# Node_ADE.net
KiCad netlist of a schematic drawn in Altium Designer
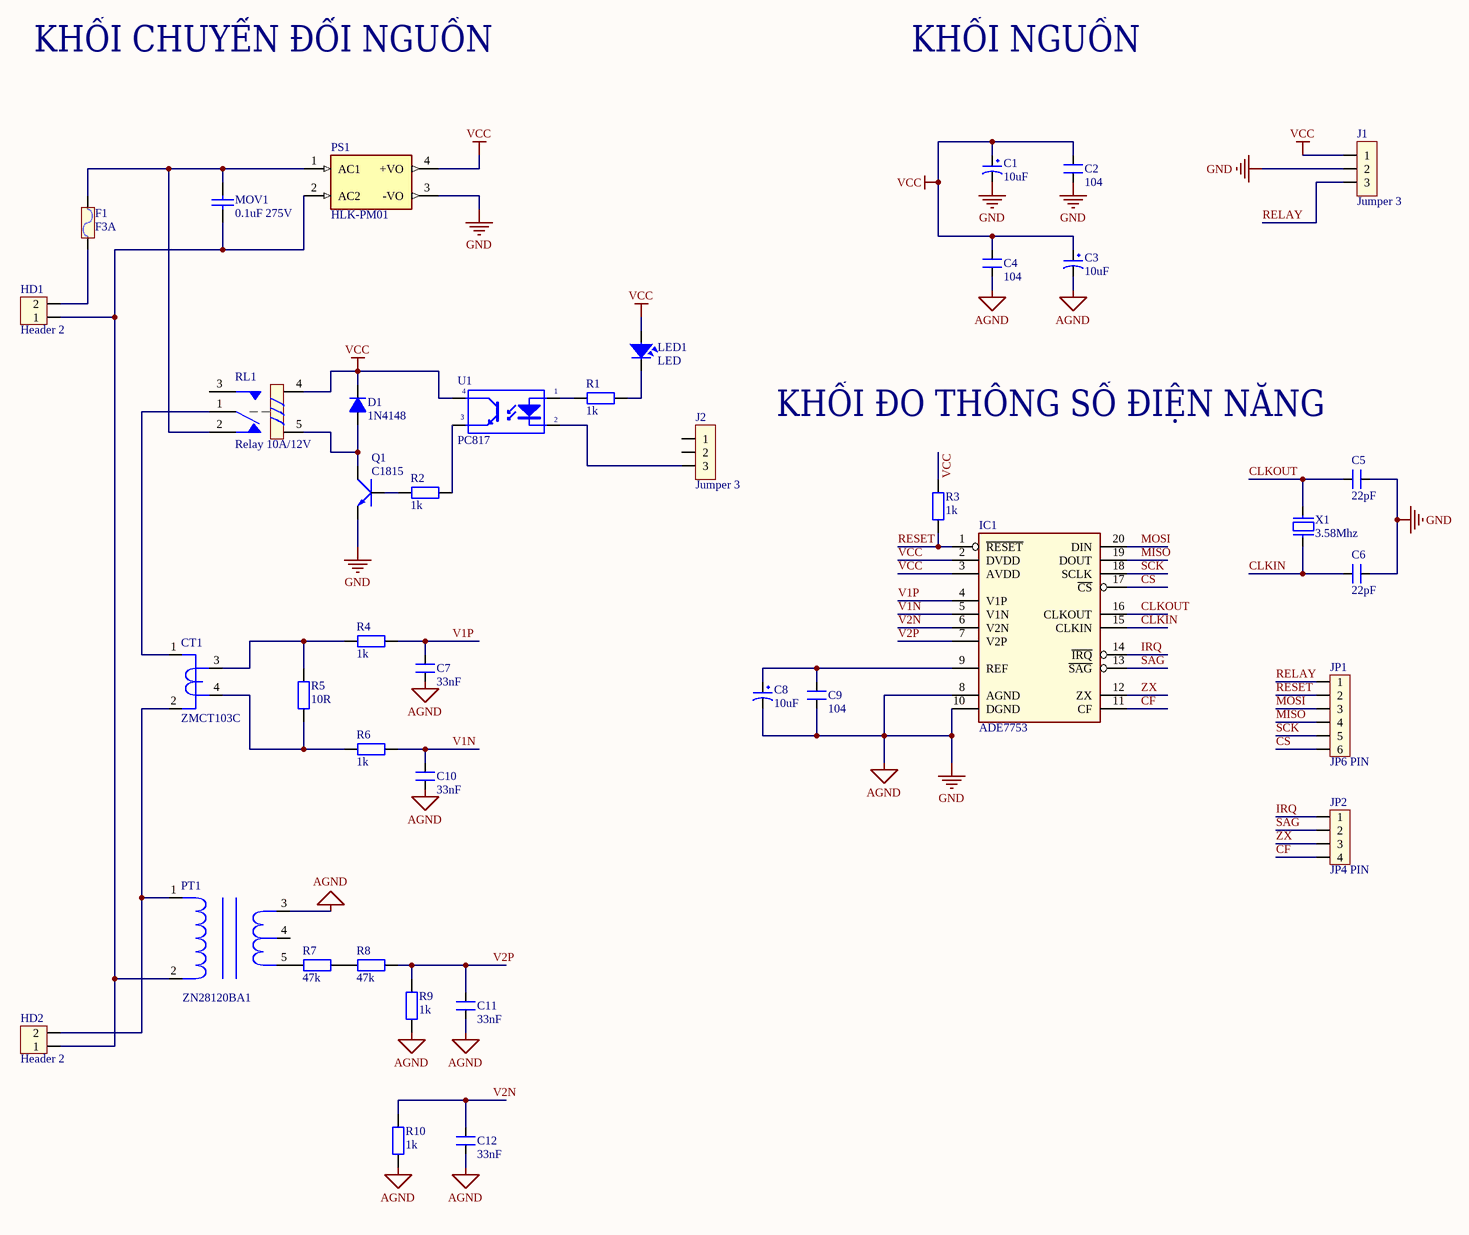
[diagram p0: Node_ADE.SchDoc]

(export (version "E")
  (design (tool "Eeschema 10.0.6"))
  (components
    (comp (ref "C1")
      (value "10uF")
      (footprint "CP1/2")
      (description "Cap P  0,1uF < 22uF , 16 - 50V")
      (libsource (lib "VioletofSun") (part "CP1"))
    )
    (comp (ref "C2")
      (value "104")
      (footprint "CN2")
      (description "Cap np 104 => 105pF")
      (libsource (lib "syhaunguyen") (part "CN2"))
    )
    (comp (ref "C3")
      (value "10uF")
      (footprint "CP1/2")
      (description "Cap P  0,1uF < 22uF , 16 - 50V")
      (libsource (lib "VioletofSun") (part "CP1"))
    )
    (comp (ref "C4")
      (value "104")
      (footprint "CN2")
      (description "Cap np 104 => 105pF")
      (libsource (lib "syhaunguyen") (part "CN2"))
    )
    (comp (ref "C5")
      (value "22pF")
      (footprint "CN1")
      (description "Cremic For Xtal 1pF => 100pF")
      (libsource (lib "syhaunguyen") (part "CN0"))
    )
    (comp (ref "C6")
      (value "22pF")
      (footprint "CN1")
      (description "Cremic For Xtal 1pF => 100pF")
      (libsource (lib "syhaunguyen") (part "CN0"))
    )
    (comp (ref "C7")
      (value "33nF")
      (footprint "CN1")
      (description "Cremic For Xtal 1pF => 100pF")
      (libsource (lib "VioletofSun") (part "CN0"))
    )
    (comp (ref "C8")
      (value "10uF")
      (footprint "CP1/2")
      (description "Cap P  0,1uF < 22uF , 16 - 50V")
      (libsource (lib "VioletofSun") (part "CP1"))
    )
    (comp (ref "C9")
      (value "104")
      (footprint "CN2")
      (description "Cap np 104 => 105pF")
      (libsource (lib "syhaunguyen") (part "CN2"))
    )
    (comp (ref "C10")
      (value "33nF")
      (footprint "CN1")
      (description "Cremic For Xtal 1pF => 100pF")
      (libsource (lib "VioletofSun") (part "CN0"))
    )
    (comp (ref "C11")
      (value "33nF")
      (footprint "CN1")
      (description "Cremic For Xtal 1pF => 100pF")
      (libsource (lib "VioletofSun") (part "CN0"))
    )
    (comp (ref "C12")
      (value "33nF")
      (footprint "CN1")
      (description "Cremic For Xtal 1pF => 100pF")
      (libsource (lib "VioletofSun") (part "CN0"))
    )
    (comp (ref "CT1")
      (value "ZMCT103C")
      (footprint "ZMCT103C:ZMCT103C")
      (description "ZMCT103C Current Transformer 1000:1 5A/5mA")
      (libsource (lib "ZMCT103C") (part "ZMCT103C"))
    )
    (comp (ref "D1")
      (value "1N4148")
      (footprint "D0.5A")
      (description "D0.5A")
      (libsource (lib "syhaunguyen") (part "D0.5A"))
    )
    (comp (ref "F1")
      (value "F3A")
      (footprint "FUSE2")
      (description "Fuse")
      (fields (field (name "DESIGNED BY") "VanDungEvn"))
      (libsource (lib "syhaunguyen") (part "Fuse"))
    )
    (comp (ref "HD1")
      (value "Header 2")
      (footprint "HED2")
      (description "Header 2 (Green)")
      (libsource (lib "syhaunguyen") (part "Hed2"))
    )
    (comp (ref "HD2")
      (value "Header 2")
      (footprint "HED2")
      (description "Header 2 (Green)")
      (libsource (lib "syhaunguyen") (part "Hed2"))
    )
    (comp (ref "IC1")
      (value "ADE7753")
      (footprint "TSOP65-20BN")
      (description "Single-Phase Multifunction Metering IC with di/dt Sensor Interface")
      (libsource (lib "syhaunguyen") (part "ADE7753"))
    )
    (comp (ref "J1") (value "Jumper 3") (footprint "JP3") (libsource (lib "syhaunguyen") (part "JP3")))
    (comp (ref "J2") (value "Jumper 3") (footprint "JP3") (libsource (lib "syhaunguyen") (part "JP3")))
    (comp (ref "JP1") (value "JP6 PIN") (footprint "JP6") (libsource (lib "syhaunguyen") (part "JP6")))
    (comp (ref "JP2") (value "JP4 PIN") (footprint "JP4") (libsource (lib "Cty1") (part "JP4")))
    (comp (ref "LED1")
      (value "LED")
      (footprint "LED-3")
      (description "LED Single colour Green and Red")
      (libsource (lib "syhaunguyen") (part "LED"))
    )
    (comp (ref "MOV1")
      (value "0.1uF 275V")
      (footprint "CAP_1uF")
      (description "Capacitor 0.1uF 275V")
      (libsource (lib "My IC") (part "Cap DIP"))
    )
    (comp (ref "PS1")
      (value "HLK-PM01")
      (footprint "CONV_HLK-PM01")
      (fields (field (name "MF") "Hi-link") (field (name "MP") "hlk-pm01"))
      (libsource (lib "HLK-PM01") (part "HLK-PM01"))
    )
    (comp (ref "PT1")
      (value "ZN28120BA1")
      (footprint "ZN28120BA1")
      (description "220VAC / 12VAC EI28 ZN28120BA1")
      (libsource (lib "ZN28120BA1") (part "EI28 ZN28120BA1"))
    )
    (comp (ref "Q1")
      (value "C1815")
      (footprint "QTO-92")
      (description "NPN 600mW, ECB")
      (libsource (lib "VioletofSun") (part "C1815"))
    )
    (comp (ref "R1")
      (value "1k")
      (footprint "R1/4W")
      (description "Resistor 1/4W")
      (libsource (lib "syhaunguyen") (part "R1/4W"))
    )
    (comp (ref "R2")
      (value "1k")
      (footprint "R1/4W")
      (description "Resistor 1/4W")
      (libsource (lib "syhaunguyen") (part "R1/4W"))
    )
    (comp (ref "R3")
      (value "1k")
      (footprint "R1/4W")
      (description "Resistor 1/4W")
      (libsource (lib "syhaunguyen") (part "R1/4W"))
    )
    (comp (ref "R4")
      (value "1k")
      (footprint "R1/4W")
      (description "Resistor 1/4W")
      (libsource (lib "syhaunguyen") (part "R1/4W"))
    )
    (comp (ref "R5")
      (value "10R")
      (footprint "R1/2W")
      (description "Resistor 1/4W")
      (libsource (lib "syhaunguyen") (part "R1/4W"))
    )
    (comp (ref "R6")
      (value "1k")
      (footprint "R1/4W")
      (description "Resistor 1/4W")
      (libsource (lib "syhaunguyen") (part "R1/4W"))
    )
    (comp (ref "R7")
      (value "47k")
      (footprint "R1/4W")
      (description "Resistor 1/4W")
      (libsource (lib "syhaunguyen") (part "R1/4W"))
    )
    (comp (ref "R8")
      (value "47k")
      (footprint "R1/4W")
      (description "Resistor 1/4W")
      (libsource (lib "syhaunguyen") (part "R1/4W"))
    )
    (comp (ref "R9")
      (value "1k")
      (footprint "R1/4W")
      (description "Resistor 1/4W")
      (libsource (lib "syhaunguyen") (part "R1/4W"))
    )
    (comp (ref "R10")
      (value "1k")
      (footprint "R1/4W")
      (description "Resistor 1/4W")
      (libsource (lib "syhaunguyen") (part "R1/4W"))
    )
    (comp (ref "RL1")
      (value "Relay 10A/12V")
      (footprint "RL_SPDT_10A")
      (description "Relay SPDT,10A - 12VDC 5 Pin")
      (libsource (lib "syhaunguyen") (part "Relay 1"))
    )
    (comp (ref "U1")
      (value "PC817")
      (footprint "DIP4/W0.3")
      (description "Single Opto")
      (libsource (lib "syhaunguyen") (part "PC817"))
    )
    (comp (ref "X1")
      (value "3.58Mhz")
      (footprint "XT2")
      (description "Crystal For all Crystal 2pin.")
      (libsource (lib "syhaunguyen") (part "XT2"))
    )
  )
  (nets
    (net (code "2") (name "/CF") (class "Default")
      (node (ref "IC1") (pin "11") (pinfunction "CF_11") (pintype "passive"))
      (node (ref "JP2") (pin "4") (pinfunction "4_4") (pintype "passive"))
    )
    (net (code "3") (name "/CLKIN") (class "Default")
      (node (ref "C6") (pin "1") (pinfunction "1_1") (pintype "passive"))
      (node (ref "IC1") (pin "15") (pinfunction "CLKIN_15") (pintype "passive"))
      (node (ref "X1") (pin "1") (pinfunction "1_1") (pintype "passive"))
    )
    (net (code "4") (name "/CLKOUT") (class "Default")
      (node (ref "C5") (pin "1") (pinfunction "1_1") (pintype "passive"))
      (node (ref "IC1") (pin "16") (pinfunction "CLKOUT_16") (pintype "passive"))
      (node (ref "X1") (pin "2") (pinfunction "2_2") (pintype "passive"))
    )
    (net (code "5") (name "/CS") (class "Default")
      (node (ref "IC1") (pin "17") (pinfunction "~{CS}_17") (pintype "passive"))
      (node (ref "JP1") (pin "6") (pinfunction "6_6") (pintype "passive"))
    )
    (net (code "6") (name "/IRQ") (class "Default")
      (node (ref "IC1") (pin "14") (pinfunction "~{IRQ}_14") (pintype "passive"))
      (node (ref "JP2") (pin "1") (pinfunction "1_1") (pintype "passive"))
    )
    (net (code "7") (name "/MISO") (class "Default")
      (node (ref "IC1") (pin "19") (pinfunction "DOUT_19") (pintype "passive"))
      (node (ref "JP1") (pin "4") (pinfunction "4_4") (pintype "passive"))
    )
    (net (code "8") (name "/MOSI") (class "Default")
      (node (ref "IC1") (pin "20") (pinfunction "DIN_20") (pintype "passive"))
      (node (ref "JP1") (pin "3") (pinfunction "3_3") (pintype "passive"))
    )
    (net (code "9") (name "/RELAY") (class "Default")
      (node (ref "J1") (pin "3") (pinfunction "3_3") (pintype "passive"))
      (node (ref "JP1") (pin "1") (pinfunction "1_1") (pintype "passive"))
    )
    (net (code "10") (name "/RESET") (class "Default")
      (node (ref "IC1") (pin "1") (pinfunction "~{RESET}_1") (pintype "passive"))
      (node (ref "JP1") (pin "2") (pinfunction "2_2") (pintype "passive"))
      (node (ref "R3") (pin "1") (pinfunction "1_1") (pintype "passive"))
    )
    (net (code "11") (name "/SAG") (class "Default")
      (node (ref "IC1") (pin "13") (pinfunction "~{SAG}_13") (pintype "passive"))
      (node (ref "JP2") (pin "2") (pinfunction "2_2") (pintype "passive"))
    )
    (net (code "12") (name "/SCK") (class "Default")
      (node (ref "IC1") (pin "18") (pinfunction "SCLK_18") (pintype "passive"))
      (node (ref "JP1") (pin "5") (pinfunction "5_5") (pintype "passive"))
    )
    (net (code "13") (name "/V1N") (class "Default")
      (node (ref "C10") (pin "2") (pinfunction "2_2") (pintype "passive"))
      (node (ref "IC1") (pin "5") (pinfunction "V1N_5") (pintype "passive"))
      (node (ref "R6") (pin "2") (pinfunction "2_2") (pintype "passive"))
    )
    (net (code "14") (name "/V1P") (class "Default")
      (node (ref "C7") (pin "2") (pinfunction "2_2") (pintype "passive"))
      (node (ref "IC1") (pin "4") (pinfunction "V1P_4") (pintype "passive"))
      (node (ref "R4") (pin "2") (pinfunction "2_2") (pintype "passive"))
    )
    (net (code "15") (name "/V2N") (class "Default")
      (node (ref "C12") (pin "2") (pinfunction "2_2") (pintype "passive"))
      (node (ref "IC1") (pin "6") (pinfunction "V2N_6") (pintype "passive"))
      (node (ref "R10") (pin "2") (pinfunction "2_2") (pintype "passive"))
    )
    (net (code "16") (name "/V2P") (class "Default")
      (node (ref "C11") (pin "2") (pinfunction "2_2") (pintype "passive"))
      (node (ref "IC1") (pin "7") (pinfunction "V2P_7") (pintype "passive"))
      (node (ref "R8") (pin "2") (pinfunction "2_2") (pintype "passive"))
      (node (ref "R9") (pin "2") (pinfunction "2_2") (pintype "passive"))
    )
    (net (code "17") (name "/ZX") (class "Default")
      (node (ref "IC1") (pin "12") (pinfunction "ZX_12") (pintype "passive"))
      (node (ref "JP2") (pin "3") (pinfunction "3_3") (pintype "passive"))
    )
    (net (code "18") (name "AGND") (class "Default")
      (node (ref "C1") (pin "2") (pinfunction "2_2") (pintype "passive"))
      (node (ref "C10") (pin "1") (pinfunction "1_1") (pintype "passive"))
      (node (ref "C11") (pin "1") (pinfunction "1_1") (pintype "passive"))
      (node (ref "C12") (pin "1") (pinfunction "1_1") (pintype "passive"))
      (node (ref "C2") (pin "1") (pinfunction "1_1") (pintype "passive"))
      (node (ref "C3") (pin "2") (pinfunction "2_2") (pintype "passive"))
      (node (ref "C4") (pin "1") (pinfunction "1_1") (pintype "passive"))
      (node (ref "C5") (pin "2") (pinfunction "2_2") (pintype "passive"))
      (node (ref "C6") (pin "2") (pinfunction "2_2") (pintype "passive"))
      (node (ref "C7") (pin "1") (pinfunction "1_1") (pintype "passive"))
      (node (ref "C8") (pin "2") (pinfunction "2_2") (pintype "passive"))
      (node (ref "C9") (pin "1") (pinfunction "1_1") (pintype "passive"))
      (node (ref "IC1") (pin "10") (pinfunction "DGND_10") (pintype "passive"))
      (node (ref "IC1") (pin "8") (pinfunction "AGND_8") (pintype "passive"))
      (node (ref "J1") (pin "2") (pinfunction "2_2") (pintype "passive"))
      (node (ref "PS1") (pin "3") (pinfunction "-VO_3") (pintype "output"))
      (node (ref "PT1") (pin "3") (pinfunction "3_3") (pintype "passive"))
      (node (ref "Q1") (pin "1") (pinfunction "E_1") (pintype "passive"))
      (node (ref "R10") (pin "1") (pinfunction "1_1") (pintype "passive"))
      (node (ref "R9") (pin "1") (pinfunction "1_1") (pintype "passive"))
    )
    (net (code "19") (name "Net-(CT1-Pad1)") (class "Default")
      (node (ref "CT1") (pin "1") (pinfunction "1_1") (pintype "passive"))
      (node (ref "RL1") (pin "1") (pinfunction "1_1") (pintype "passive"))
    )
    (net (code "20") (name "Net-(CT1-Pad2)") (class "Default")
      (node (ref "CT1") (pin "2") (pinfunction "2_2") (pintype "passive"))
      (node (ref "HD2") (pin "2") (pinfunction "2_2") (pintype "passive"))
      (node (ref "PT1") (pin "1") (pinfunction "1_1") (pintype "passive"))
    )
    (net (code "21") (name "Net-(CT1-Pad3)") (class "Default")
      (node (ref "CT1") (pin "3") (pinfunction "3_3") (pintype "passive"))
      (node (ref "R4") (pin "1") (pinfunction "1_1") (pintype "passive"))
      (node (ref "R5") (pin "2") (pinfunction "2_2") (pintype "passive"))
    )
    (net (code "22") (name "Net-(CT1-Pad4)") (class "Default")
      (node (ref "CT1") (pin "4") (pinfunction "4_4") (pintype "passive"))
      (node (ref "R5") (pin "1") (pinfunction "1_1") (pintype "passive"))
      (node (ref "R6") (pin "1") (pinfunction "1_1") (pintype "passive"))
    )
    (net (code "23") (name "Net-(D1-A)") (class "Default")
      (node (ref "D1") (pin "1") (pinfunction "A_1") (pintype "passive"))
      (node (ref "Q1") (pin "2") (pinfunction "C_2") (pintype "passive"))
      (node (ref "RL1") (pin "5") (pinfunction "5_5") (pintype "passive"))
    )
    (net (code "24") (name "Net-(F1-Pad1)") (class "Default")
      (node (ref "F1") (pin "1") (pinfunction "1_1") (pintype "passive"))
      (node (ref "HD1") (pin "2") (pinfunction "2_2") (pintype "passive"))
    )
    (net (code "25") (name "Net-(IC1-REF)") (class "Default")
      (node (ref "C8") (pin "1") (pinfunction "1_1") (pintype "passive"))
      (node (ref "C9") (pin "2") (pinfunction "2_2") (pintype "passive"))
      (node (ref "IC1") (pin "9") (pinfunction "REF_9") (pintype "passive"))
    )
    (net (code "26") (name "Net-(LED1-Pad2)") (class "Default")
      (node (ref "LED1") (pin "2") (pinfunction "2_2") (pintype "passive"))
      (node (ref "R1") (pin "2") (pinfunction "2_2") (pintype "passive"))
    )
    (net (code "27") (name "Net-(PS1-AC1)") (class "Default")
      (node (ref "F1") (pin "2") (pinfunction "2_2") (pintype "passive"))
      (node (ref "MOV1") (pin "1") (pinfunction "1_1") (pintype "passive"))
      (node (ref "PS1") (pin "1") (pinfunction "AC1_1") (pintype "input"))
      (node (ref "RL1") (pin "2") (pinfunction "2_2") (pintype "passive"))
    )
    (net (code "28") (name "Net-(PS1-AC2)") (class "Default")
      (node (ref "HD1") (pin "1") (pinfunction "1_1") (pintype "passive"))
      (node (ref "HD2") (pin "1") (pinfunction "1_1") (pintype "passive"))
      (node (ref "MOV1") (pin "2") (pinfunction "2_2") (pintype "passive"))
      (node (ref "PS1") (pin "2") (pinfunction "AC2_2") (pintype "input"))
      (node (ref "PT1") (pin "2") (pinfunction "2_2") (pintype "passive"))
    )
    (net (code "29") (name "Net-(PT1-Pad5)") (class "Default")
      (node (ref "PT1") (pin "5") (pinfunction "5_5") (pintype "passive"))
      (node (ref "R7") (pin "1") (pinfunction "1_1") (pintype "passive"))
    )
    (net (code "30") (name "Net-(Q1-B)") (class "Default")
      (node (ref "Q1") (pin "3") (pinfunction "B_3") (pintype "passive"))
      (node (ref "R2") (pin "1") (pinfunction "1_1") (pintype "passive"))
    )
    (net (code "31") (name "Net-(R7-Pad2)") (class "Default")
      (node (ref "R7") (pin "2") (pinfunction "2_2") (pintype "passive"))
      (node (ref "R8") (pin "1") (pinfunction "1_1") (pintype "passive"))
    )
    (net (code "32") (name "Net-(U1-A)") (class "Default")
      (node (ref "R1") (pin "1") (pinfunction "1_1") (pintype "passive"))
      (node (ref "U1") (pin "1") (pinfunction "A_1") (pintype "passive"))
    )
    (net (code "33") (name "Net-(U1-E)") (class "Default")
      (node (ref "R2") (pin "2") (pinfunction "2_2") (pintype "passive"))
      (node (ref "U1") (pin "3") (pinfunction "E_3") (pintype "passive"))
    )
    (net (code "34") (name "Net-(U1-K)") (class "Default")
      (node (ref "J2") (pin "3") (pinfunction "3_3") (pintype "passive"))
      (node (ref "U1") (pin "2") (pinfunction "K_2") (pintype "passive"))
    )
    (net (code "35") (name "VCC") (class "Default")
      (node (ref "C1") (pin "1") (pinfunction "1_1") (pintype "passive"))
      (node (ref "C2") (pin "2") (pinfunction "2_2") (pintype "passive"))
      (node (ref "C3") (pin "1") (pinfunction "1_1") (pintype "passive"))
      (node (ref "C4") (pin "2") (pinfunction "2_2") (pintype "passive"))
      (node (ref "D1") (pin "2") (pinfunction "K_2") (pintype "passive"))
      (node (ref "IC1") (pin "2") (pinfunction "DVDD_2") (pintype "passive"))
      (node (ref "IC1") (pin "3") (pinfunction "AVDD_3") (pintype "passive"))
      (node (ref "J1") (pin "1") (pinfunction "1_1") (pintype "passive"))
      (node (ref "LED1") (pin "1") (pinfunction "1_1") (pintype "passive"))
      (node (ref "PS1") (pin "4") (pinfunction "+VO_4") (pintype "output"))
      (node (ref "R3") (pin "2") (pinfunction "2_2") (pintype "passive"))
      (node (ref "RL1") (pin "4") (pinfunction "4_4") (pintype "passive"))
      (node (ref "U1") (pin "4") (pinfunction "C_4") (pintype "passive"))
    )
    (net (code "36") (name "unconnected-(J2-Pad1)") (class "Default")
      (node (ref "J2") (pin "1") (pinfunction "1_1") (pintype "passive"))
    )
    (net (code "37") (name "unconnected-(J2-Pad2)") (class "Default")
      (node (ref "J2") (pin "2") (pinfunction "2_2") (pintype "passive"))
    )
    (net (code "38") (name "unconnected-(PT1-Pad4)") (class "Default")
      (node (ref "PT1") (pin "4") (pinfunction "4_4") (pintype "passive"))
    )
    (net (code "39") (name "unconnected-(RL1-Pad3)") (class "Default")
      (node (ref "RL1") (pin "3") (pinfunction "3_3") (pintype "passive"))
    )
  )
)
